# blinker.net
KiCad netlist of a schematic drawn in EAGLE
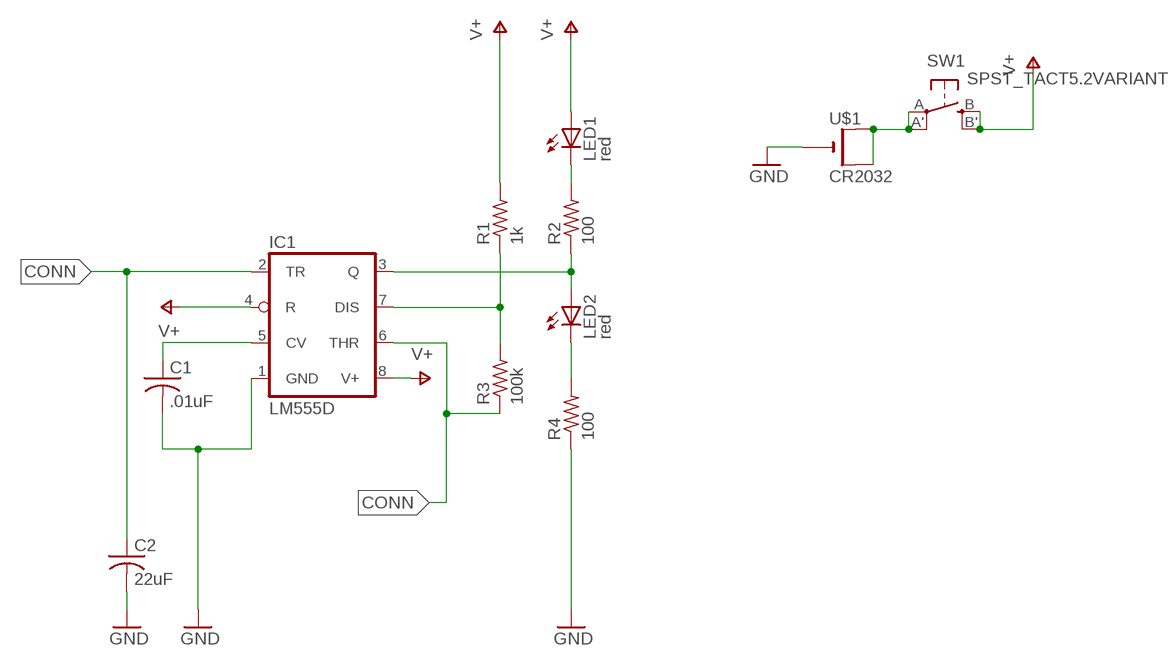
[diagram p0: schematic, sheet 1]

(export (version "E")
  (design (tool "Eeschema 10.0.6"))
  (components
    (comp (ref "C1")
      (value ".01uF")
      (footprint "eagle-import:C0805")
      (libsource (lib "eagle-import") (part "C-USC0805"))
    )
    (comp (ref "C2")
      (value "22uF")
      (footprint "eagle-import:C0805")
      (libsource (lib "eagle-import") (part "C-USC0805"))
    )
    (comp (ref "IC1")
      (value "LM555D")
      (footprint "eagle-import:SO08")
      (libsource (lib "eagle-import") (part "555DLM"))
    )
    (comp (ref "LED1")
      (value "red")
      (footprint "eagle-import:CHIPLED_0805")
      (libsource (lib "eagle-import") (part "LEDCHIPLED_0805"))
    )
    (comp (ref "LED2")
      (value "red")
      (footprint "eagle-import:CHIPLED_0805")
      (libsource (lib "eagle-import") (part "LEDCHIPLED_0805"))
    )
    (comp (ref "R1")
      (value "1k")
      (footprint "eagle-import:R0805")
      (libsource (lib "eagle-import") (part "R-US_R0805"))
    )
    (comp (ref "R2")
      (value "100")
      (footprint "eagle-import:R0805")
      (libsource (lib "eagle-import") (part "R-US_R0805"))
    )
    (comp (ref "R3")
      (value "100k")
      (footprint "eagle-import:R0805")
      (libsource (lib "eagle-import") (part "R-US_R0805"))
    )
    (comp (ref "R4")
      (value "100")
      (footprint "eagle-import:R0805")
      (libsource (lib "eagle-import") (part "R-US_R0805"))
    )
    (comp (ref "SW1")
      (value "SPST_TACT5.2VARIANT")
      (footprint "eagle-import:5.2X5.2")
      (libsource (lib "eagle-import") (part "SPST_TACT5.2VARIANT"))
    )
    (comp (ref "U$1")
      (value "CR2032")
      (footprint "eagle-import:CR2032-SMD")
      (libsource (lib "eagle-import") (part "CR2032SMT"))
    )
  )
  (nets
    (net (code "1") (name "CONN") (class "Default")
      (node (ref "C2") (pin "1") (pinfunction "1_1") (pintype "passive"))
      (node (ref "IC1") (pin "2") (pinfunction "TR_2") (pintype "input"))
      (node (ref "IC1") (pin "6") (pinfunction "THR_6") (pintype "input"))
      (node (ref "R3") (pin "1") (pinfunction "1_1") (pintype "passive"))
    )
    (net (code "2") (name "GND") (class "Default")
      (node (ref "C1") (pin "2") (pinfunction "2_2") (pintype "passive"))
      (node (ref "C2") (pin "2") (pinfunction "2_2") (pintype "passive"))
      (node (ref "IC1") (pin "1") (pinfunction "GND_1") (pintype "power_in"))
      (node (ref "R4") (pin "1") (pinfunction "1_1") (pintype "passive"))
      (node (ref "U$1") (pin "-") (pinfunction "-_-") (pintype "passive"))
    )
    (net (code "3") (name "Net-(IC1-CV)") (class "Default")
      (node (ref "C1") (pin "1") (pinfunction "1_1") (pintype "passive"))
      (node (ref "IC1") (pin "5") (pinfunction "CV_5") (pintype "input"))
    )
    (net (code "4") (name "Net-(IC1-DIS)") (class "Default")
      (node (ref "IC1") (pin "7") (pinfunction "DIS_7") (pintype "input"))
      (node (ref "R1") (pin "1") (pinfunction "1_1") (pintype "passive"))
      (node (ref "R3") (pin "2") (pinfunction "2_2") (pintype "passive"))
    )
    (net (code "5") (name "Net-(IC1-Q)") (class "Default")
      (node (ref "IC1") (pin "3") (pinfunction "Q_3") (pintype "output"))
      (node (ref "LED2") (pin "A") (pinfunction "A_A") (pintype "passive"))
      (node (ref "R2") (pin "1") (pinfunction "1_1") (pintype "passive"))
    )
    (net (code "6") (name "Net-(LED1-PadC)") (class "Default")
      (node (ref "LED1") (pin "C") (pinfunction "C_C") (pintype "passive"))
      (node (ref "R2") (pin "2") (pinfunction "2_2") (pintype "passive"))
    )
    (net (code "7") (name "Net-(LED2-PadC)") (class "Default")
      (node (ref "LED2") (pin "C") (pinfunction "C_C") (pintype "passive"))
      (node (ref "R4") (pin "2") (pinfunction "2_2") (pintype "passive"))
    )
    (net (code "8") (name "Net-(SW1-P)") (class "Default")
      (node (ref "SW1") (pin "A") (pinfunction "P_A") (pintype "passive"))
      (node (ref "SW1") (pin "A'") (pinfunction "P1_A'") (pintype "passive"))
      (node (ref "U$1") (pin "+$1") (pinfunction "+_+$1") (pintype "passive"))
      (node (ref "U$1") (pin "+$2") (pinfunction "+1_+$2") (pintype "passive"))
    )
    (net (code "9") (name "V+") (class "Default")
      (node (ref "IC1") (pin "4") (pinfunction "R_4") (pintype "input"))
      (node (ref "IC1") (pin "8") (pinfunction "V+_8") (pintype "power_in"))
      (node (ref "LED1") (pin "A") (pinfunction "A_A") (pintype "passive"))
      (node (ref "R1") (pin "2") (pinfunction "2_2") (pintype "passive"))
      (node (ref "SW1") (pin "B") (pinfunction "S_B") (pintype "passive"))
      (node (ref "SW1") (pin "B'") (pinfunction "S1_B'") (pintype "passive"))
    )
  )
)
